# MCP23017_-_ENCODER.net
KiCad netlist of a schematic drawn in Altium Designer
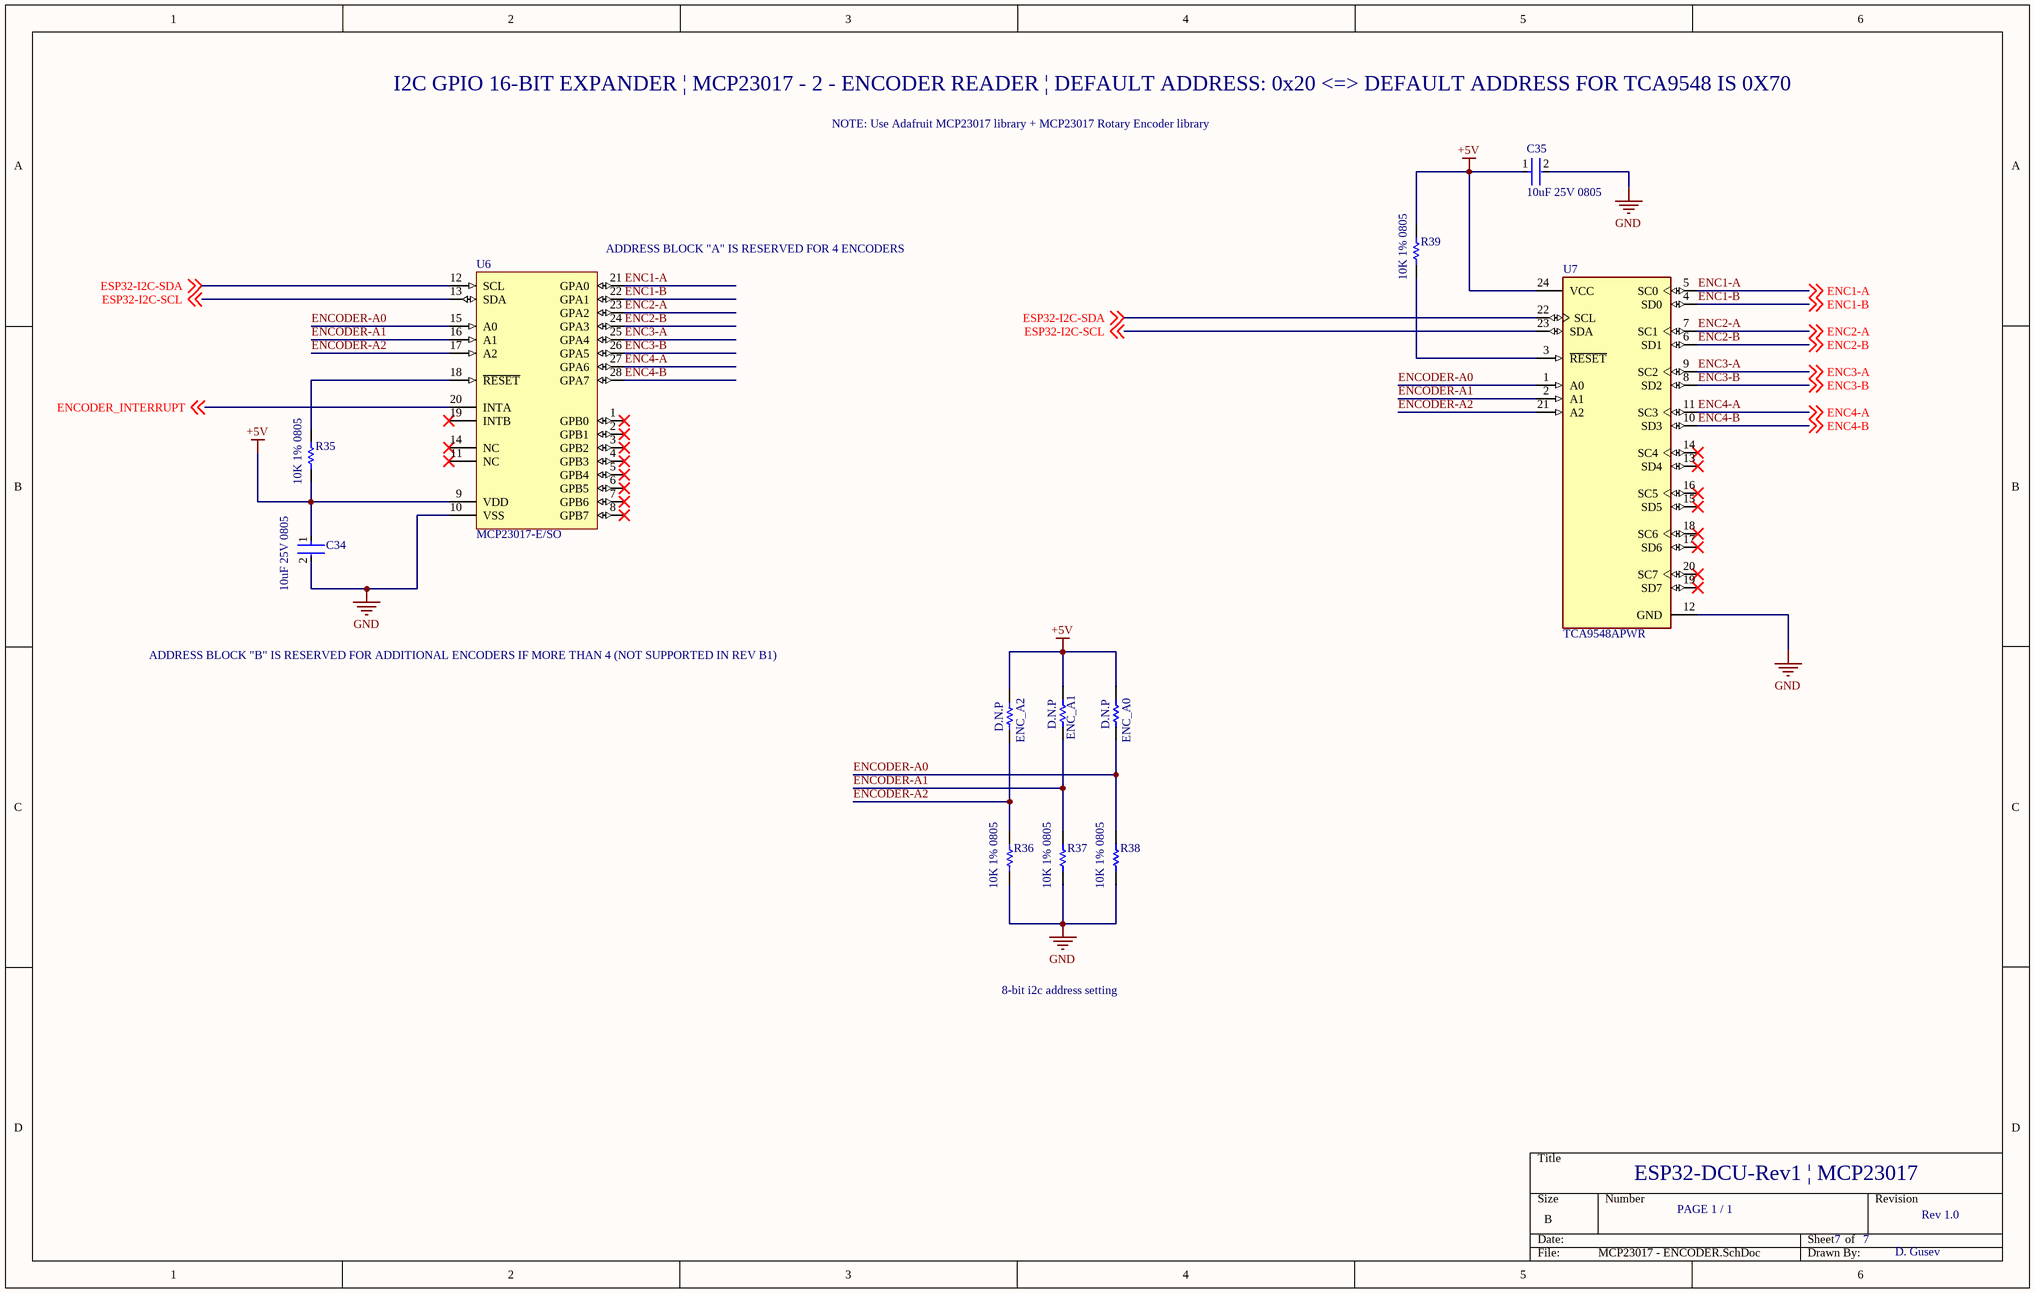
[diagram p0: MCP23017 - ENCODER.SchDoc]

(export (version "E")
  (design (tool "Eeschema 10.0.6"))
  (components
    (comp (ref "C34")
      (value "10uF 25V 0805")
      (footprint "FP-GRM21B-0_15-IPC_B")
      (description "Chip Multilayer Ceramic Capacitors for General Purpose, 0805, 10uF, X5R, 15%, 10%, 25V")
      (fields (field (name "VOLTAGE") "25V") (field (name "TOLERANCE") "10%"))
      (libsource (lib "Altium Content Vault") (part "b4654b650e69147ec39a6b967a45e02"))
    )
    (comp (ref "C35")
      (value "10uF 25V 0805")
      (footprint "FP-GRM21B-0_15-IPC_B")
      (description "Chip Multilayer Ceramic Capacitors for General Purpose, 0805, 10uF, X5R, 15%, 10%, 25V")
      (fields (field (name "VOLTAGE") "25V") (field (name "TOLERANCE") "10%"))
      (libsource (lib "Altium Content Vault") (part "b4654b650e69147ec39a6b967a45e02"))
    )
    (comp (ref "ENC_A0")
      (value "D.N.P")
      (footprint "RESC2013X60X35LL10T20")
      (description "Chip Resistor, 1 Ohm, +/- 1%, 125 mW, -55 to 155 degC, 0805 (2012 Metric), RoHS, Tape and Reel")
      (fields (field (name "MANUFACTURER") "Yageo"))
      (libsource (lib "Altium Content Vault") (part "RES-2"))
    )
    (comp (ref "ENC_A1")
      (value "D.N.P")
      (footprint "RESC2013X60X35LL10T20")
      (description "Chip Resistor, 1 Ohm, +/- 1%, 125 mW, -55 to 155 degC, 0805 (2012 Metric), RoHS, Tape and Reel")
      (fields (field (name "MANUFACTURER") "Yageo"))
      (libsource (lib "Altium Content Vault") (part "RES-2"))
    )
    (comp (ref "ENC_A2")
      (value "D.N.P")
      (footprint "RESC2013X60X35LL10T20")
      (description "Chip Resistor, 1 Ohm, +/- 1%, 125 mW, -55 to 155 degC, 0805 (2012 Metric), RoHS, Tape and Reel")
      (fields (field (name "MANUFACTURER") "Yageo"))
      (libsource (lib "Altium Content Vault") (part "RES-2"))
    )
    (comp (ref "R35")
      (value "10K 1% 0805")
      (footprint "RESC2013X60X35ML10T20")
      (description "Chip Resistor, 10 KOhm, +/- 5%, 0.125 W, -55 to 155 degC, 0805 (2012 Metric), RoHS, Tape and Reel")
      (fields (field (name "MANUFACTURER") "Yageo"))
      (libsource (lib "Altium Content Vault") (part "RES-2"))
    )
    (comp (ref "R36")
      (value "10K 1% 0805")
      (footprint "RESC2013X60X35ML10T20")
      (description "Chip Resistor, 10 KOhm, +/- 5%, 0.125 W, -55 to 155 degC, 0805 (2012 Metric), RoHS, Tape and Reel")
      (fields (field (name "MANUFACTURER") "Yageo"))
      (libsource (lib "Altium Content Vault") (part "RES-2"))
    )
    (comp (ref "R37")
      (value "10K 1% 0805")
      (footprint "RESC2013X60X35ML10T20")
      (description "Chip Resistor, 10 KOhm, +/- 5%, 0.125 W, -55 to 155 degC, 0805 (2012 Metric), RoHS, Tape and Reel")
      (fields (field (name "MANUFACTURER") "Yageo"))
      (libsource (lib "Altium Content Vault") (part "RES-2"))
    )
    (comp (ref "R38")
      (value "10K 1% 0805")
      (footprint "RESC2013X60X35ML10T20")
      (description "Chip Resistor, 10 KOhm, +/- 5%, 0.125 W, -55 to 155 degC, 0805 (2012 Metric), RoHS, Tape and Reel")
      (fields (field (name "MANUFACTURER") "Yageo"))
      (libsource (lib "Altium Content Vault") (part "RES-2"))
    )
    (comp (ref "R39")
      (value "10K 1% 0805")
      (footprint "RESC2013X60X35ML10T20")
      (description "Chip Resistor, 10 KOhm, +/- 5%, 0.125 W, -55 to 155 degC, 0805 (2012 Metric), RoHS, Tape and Reel")
      (fields (field (name "MANUFACTURER") "Yageo"))
      (libsource (lib "Altium Content Vault") (part "RES-2"))
    )
    (comp (ref "U6")
      (value "MCP23017-E/SO")
      (footprint "SOIC-SO28_N")
      (description "16-Bit I/O Expander with Serial Interface, 28-Pin SOIC, Extended Temperature")
      (libsource (lib "Altium Content Vault") (part "PR-BUSIC-MCP23017-28"))
    )
    (comp (ref "U7")
      (value "TCA9548APWR")
      (footprint "FP-PW0024A-MFG")
      (description "IC I2C SW 8CH W/RESET 24TSSOP")
      (fields
        (field (name "MANUFACTURER") "Texas Instruments")
        (field (name "OCTOPART") "https://octopart.com/tca9548apwr-texas+instruments-22266789")
      )
      (libsource (lib "Altium Content Vault") (part "aab65143522579f0e88a32f493a4230"))
    )
  )
  (nets
    (net (code "1") (name "+5V") (class "Default")
      (node (ref "C34") (pin "1") (pinfunction "1_1") (pintype "passive"))
      (node (ref "C35") (pin "1") (pinfunction "1_1") (pintype "passive"))
      (node (ref "ENC_A0") (pin "2") (pinfunction "2_2") (pintype "passive"))
      (node (ref "ENC_A1") (pin "2") (pinfunction "2_2") (pintype "passive"))
      (node (ref "ENC_A2") (pin "2") (pinfunction "2_2") (pintype "passive"))
      (node (ref "R35") (pin "1") (pinfunction "1_1") (pintype "passive"))
      (node (ref "R39") (pin "2") (pinfunction "2_2") (pintype "passive"))
      (node (ref "U6") (pin "9") (pinfunction "VDD_9") (pintype "power_in"))
      (node (ref "U7") (pin "24") (pinfunction "VCC_24") (pintype "power_in"))
    )
    (net (code "2") (name "/ENCODER-A0") (class "Default")
      (node (ref "ENC_A0") (pin "1") (pinfunction "1_1") (pintype "passive"))
      (node (ref "R38") (pin "1") (pinfunction "1_1") (pintype "passive"))
      (node (ref "U6") (pin "15") (pinfunction "A0_15") (pintype "input"))
      (node (ref "U7") (pin "1") (pinfunction "A0_1") (pintype "input"))
    )
    (net (code "3") (name "/ENCODER-A1") (class "Default")
      (node (ref "ENC_A1") (pin "1") (pinfunction "1_1") (pintype "passive"))
      (node (ref "R37") (pin "1") (pinfunction "1_1") (pintype "passive"))
      (node (ref "U6") (pin "16") (pinfunction "A1_16") (pintype "input"))
      (node (ref "U7") (pin "2") (pinfunction "A1_2") (pintype "input"))
    )
    (net (code "4") (name "/ENCODER-A2") (class "Default")
      (node (ref "ENC_A2") (pin "1") (pinfunction "1_1") (pintype "passive"))
      (node (ref "R36") (pin "1") (pinfunction "1_1") (pintype "passive"))
      (node (ref "U6") (pin "17") (pinfunction "A2_17") (pintype "input"))
      (node (ref "U7") (pin "21") (pinfunction "A2_21") (pintype "input"))
    )
    (net (code "5") (name "ENC1-A") (class "Default")
      (node (ref "U6") (pin "21") (pinfunction "GPA0_21") (pintype "bidirectional"))
      (node (ref "U7") (pin "5") (pinfunction "SC0_5") (pintype "bidirectional"))
    )
    (net (code "6") (name "ENC1-B") (class "Default")
      (node (ref "U6") (pin "22") (pinfunction "GPA1_22") (pintype "bidirectional"))
      (node (ref "U7") (pin "4") (pinfunction "SD0_4") (pintype "bidirectional"))
    )
    (net (code "7") (name "ENC2-A") (class "Default")
      (node (ref "U6") (pin "23") (pinfunction "GPA2_23") (pintype "bidirectional"))
      (node (ref "U7") (pin "7") (pinfunction "SC1_7") (pintype "bidirectional"))
    )
    (net (code "8") (name "ENC2-B") (class "Default")
      (node (ref "U6") (pin "24") (pinfunction "GPA3_24") (pintype "bidirectional"))
      (node (ref "U7") (pin "6") (pinfunction "SD1_6") (pintype "bidirectional"))
    )
    (net (code "9") (name "ENC3-A") (class "Default")
      (node (ref "U6") (pin "25") (pinfunction "GPA4_25") (pintype "bidirectional"))
      (node (ref "U7") (pin "9") (pinfunction "SC2_9") (pintype "bidirectional"))
    )
    (net (code "10") (name "ENC3-B") (class "Default")
      (node (ref "U6") (pin "26") (pinfunction "GPA5_26") (pintype "bidirectional"))
      (node (ref "U7") (pin "8") (pinfunction "SD2_8") (pintype "bidirectional"))
    )
    (net (code "11") (name "ENC4-A") (class "Default")
      (node (ref "U6") (pin "27") (pinfunction "GPA6_27") (pintype "bidirectional"))
      (node (ref "U7") (pin "11") (pinfunction "SC3_11") (pintype "bidirectional"))
    )
    (net (code "12") (name "ENC4-B") (class "Default")
      (node (ref "U6") (pin "28") (pinfunction "GPA7_28") (pintype "bidirectional"))
      (node (ref "U7") (pin "10") (pinfunction "SD3_10") (pintype "bidirectional"))
    )
    (net (code "13") (name "ENCODER_INTERRUPT") (class "Default")
      (node (ref "U6") (pin "20") (pinfunction "INTA_20") (pintype "open_collector"))
    )
    (net (code "14") (name "ESP32-I2C-SCL") (class "Default")
      (node (ref "U6") (pin "13") (pinfunction "SDA_13") (pintype "bidirectional"))
      (node (ref "U7") (pin "23") (pinfunction "SDA_23") (pintype "bidirectional"))
    )
    (net (code "15") (name "ESP32-I2C-SDA") (class "Default")
      (node (ref "U6") (pin "12") (pinfunction "SCL_12") (pintype "input"))
      (node (ref "U7") (pin "22") (pinfunction "SCL_22") (pintype "bidirectional"))
    )
    (net (code "16") (name "GND") (class "Default")
      (node (ref "C34") (pin "2") (pinfunction "2_2") (pintype "passive"))
      (node (ref "C35") (pin "2") (pinfunction "2_2") (pintype "passive"))
      (node (ref "R36") (pin "2") (pinfunction "2_2") (pintype "passive"))
      (node (ref "R37") (pin "2") (pinfunction "2_2") (pintype "passive"))
      (node (ref "R38") (pin "2") (pinfunction "2_2") (pintype "passive"))
      (node (ref "U6") (pin "10") (pinfunction "VSS_10") (pintype "power_in"))
      (node (ref "U7") (pin "12") (pinfunction "GND_12") (pintype "power_in"))
    )
    (net (code "17") (name "Net-(U6-~{RESET})") (class "Default")
      (node (ref "R35") (pin "2") (pinfunction "2_2") (pintype "passive"))
      (node (ref "U6") (pin "18") (pinfunction "~{RESET}_18") (pintype "input"))
    )
    (net (code "18") (name "Net-(U7-~{RESET})") (class "Default")
      (node (ref "R39") (pin "1") (pinfunction "1_1") (pintype "passive"))
      (node (ref "U7") (pin "3") (pinfunction "~{RESET}_3") (pintype "input"))
    )
    (net (code "19") (name "unconnected-(U6-GPB0-Pad1)") (class "Default")
      (node (ref "U6") (pin "1") (pinfunction "GPB0_1") (pintype "bidirectional+no_connect"))
    )
    (net (code "20") (name "unconnected-(U6-GPB1-Pad2)") (class "Default")
      (node (ref "U6") (pin "2") (pinfunction "GPB1_2") (pintype "bidirectional+no_connect"))
    )
    (net (code "21") (name "unconnected-(U6-GPB2-Pad3)") (class "Default")
      (node (ref "U6") (pin "3") (pinfunction "GPB2_3") (pintype "bidirectional+no_connect"))
    )
    (net (code "22") (name "unconnected-(U6-GPB3-Pad4)") (class "Default")
      (node (ref "U6") (pin "4") (pinfunction "GPB3_4") (pintype "bidirectional+no_connect"))
    )
    (net (code "23") (name "unconnected-(U6-GPB4-Pad5)") (class "Default")
      (node (ref "U6") (pin "5") (pinfunction "GPB4_5") (pintype "bidirectional+no_connect"))
    )
    (net (code "24") (name "unconnected-(U6-GPB5-Pad6)") (class "Default")
      (node (ref "U6") (pin "6") (pinfunction "GPB5_6") (pintype "bidirectional+no_connect"))
    )
    (net (code "25") (name "unconnected-(U6-GPB6-Pad7)") (class "Default")
      (node (ref "U6") (pin "7") (pinfunction "GPB6_7") (pintype "bidirectional+no_connect"))
    )
    (net (code "26") (name "unconnected-(U6-GPB7-Pad8)") (class "Default")
      (node (ref "U6") (pin "8") (pinfunction "GPB7_8") (pintype "bidirectional+no_connect"))
    )
    (net (code "27") (name "unconnected-(U6-INTB-Pad19)") (class "Default")
      (node (ref "U6") (pin "19") (pinfunction "INTB_19") (pintype "open_collector+no_connect"))
    )
    (net (code "28") (name "unconnected-(U6-NC-Pad11)") (class "Default")
      (node (ref "U6") (pin "11") (pinfunction "NC_11") (pintype "passive+no_connect"))
    )
    (net (code "29") (name "unconnected-(U6-NC-Pad14)") (class "Default")
      (node (ref "U6") (pin "14") (pinfunction "NC_14") (pintype "passive+no_connect"))
    )
    (net (code "30") (name "unconnected-(U7-SC4-Pad14)") (class "Default")
      (node (ref "U7") (pin "14") (pinfunction "SC4_14") (pintype "bidirectional+no_connect"))
    )
    (net (code "31") (name "unconnected-(U7-SC5-Pad16)") (class "Default")
      (node (ref "U7") (pin "16") (pinfunction "SC5_16") (pintype "bidirectional+no_connect"))
    )
    (net (code "32") (name "unconnected-(U7-SC6-Pad18)") (class "Default")
      (node (ref "U7") (pin "18") (pinfunction "SC6_18") (pintype "bidirectional+no_connect"))
    )
    (net (code "33") (name "unconnected-(U7-SC7-Pad20)") (class "Default")
      (node (ref "U7") (pin "20") (pinfunction "SC7_20") (pintype "bidirectional+no_connect"))
    )
    (net (code "34") (name "unconnected-(U7-SD4-Pad13)") (class "Default")
      (node (ref "U7") (pin "13") (pinfunction "SD4_13") (pintype "bidirectional+no_connect"))
    )
    (net (code "35") (name "unconnected-(U7-SD5-Pad15)") (class "Default")
      (node (ref "U7") (pin "15") (pinfunction "SD5_15") (pintype "bidirectional+no_connect"))
    )
    (net (code "36") (name "unconnected-(U7-SD6-Pad17)") (class "Default")
      (node (ref "U7") (pin "17") (pinfunction "SD6_17") (pintype "bidirectional+no_connect"))
    )
    (net (code "37") (name "unconnected-(U7-SD7-Pad19)") (class "Default")
      (node (ref "U7") (pin "19") (pinfunction "SD7_19") (pintype "bidirectional+no_connect"))
    )
  )
)
